# RoboRIOSPIBreakout.net
KiCad netlist of a schematic drawn in Altium Designer
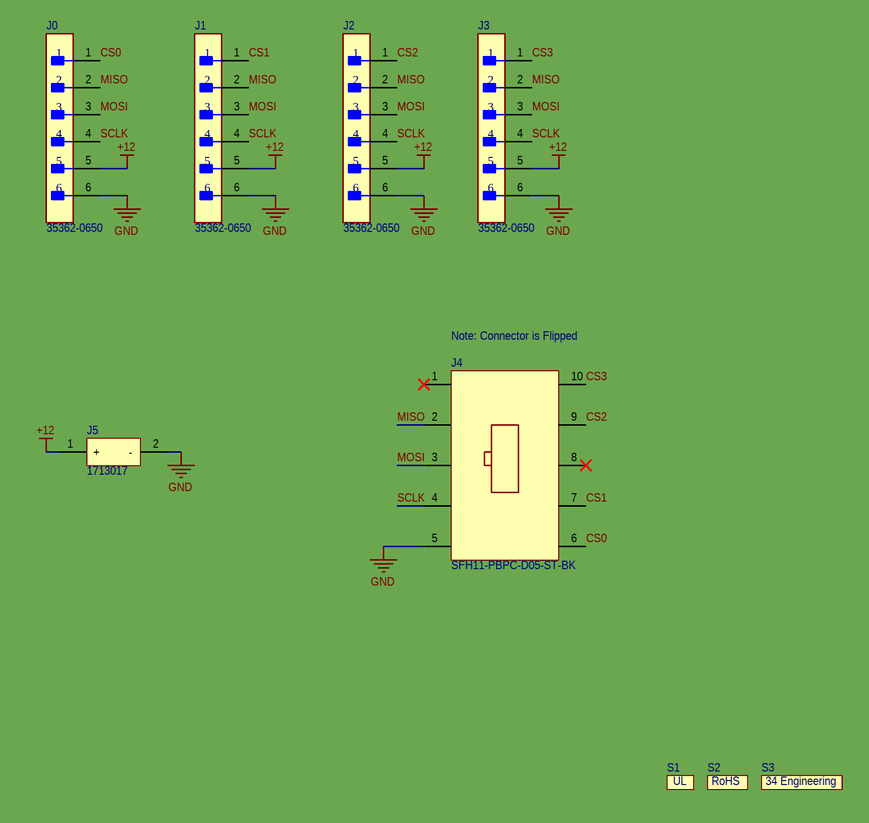
[diagram p0: RoboRIOSPIBreakout.SchDoc]

(export (version "E")
  (design (tool "Eeschema 10.0.6"))
  (components
    (comp (ref "J0")
      (value "35362-0650")
      (footprint "FP-35362-0650-MFG")
      (description "CONN HEADER VERT 6POS 2MM")
      (libsource (lib "Altium Content Vault") (part "f2cb566baf1c37ab5a3b8e90bbeafd6"))
    )
    (comp (ref "J1")
      (value "35362-0650")
      (footprint "FP-35362-0650-MFG")
      (description "CONN HEADER VERT 6POS 2MM")
      (libsource (lib "Altium Content Vault") (part "f2cb566baf1c37ab5a3b8e90bbeafd6"))
    )
    (comp (ref "J2")
      (value "35362-0650")
      (footprint "FP-35362-0650-MFG")
      (description "CONN HEADER VERT 6POS 2MM")
      (libsource (lib "Altium Content Vault") (part "f2cb566baf1c37ab5a3b8e90bbeafd6"))
    )
    (comp (ref "J3")
      (value "35362-0650")
      (footprint "FP-35362-0650-MFG")
      (description "CONN HEADER VERT 6POS 2MM")
      (libsource (lib "Altium Content Vault") (part "f2cb566baf1c37ab5a3b8e90bbeafd6"))
    )
    (comp (ref "J4")
      (value "SFH11-PBPC-D05-ST-BK")
      (footprint "SFH11-PBPC-D05-ST-BK")
      (description "Female, 10C, Straight .100\"CC; No Mt. w/Center Polarizing Key; PBT, Brass, Gold Flash, 105 C")
      (fields (field (name "MANUFACTURER") "Sullins"))
      (libsource (lib "Virtex") (part "SFH11-PBPC-D05-ST-BK"))
    )
    (comp (ref "J5")
      (value "1713017")
      (footprint "1713017")
      (description "PCB Terminal Push-In 3.5mm 16AWG 250V 8A 2 Position Combicon Compact Series")
      (fields (field (name "MANUFACTURER") "Phoenix Contact") (field (name "VOLTAGE") "300V"))
      (libsource (lib "Virtex") (part "1713017"))
    )
    (comp (ref "S1") (value "~") (footprint "UL") (libsource (lib "Virtex") (part "UL")))
    (comp (ref "S2") (value "~") (footprint "RoHS") (libsource (lib "Virtex") (part "RoHS")))
    (comp (ref "S3")
      (value "~")
      (footprint "34EngineeringLogo")
      (description "34 Engineering Silkscreen Logo")
      (libsource (lib "Virtex") (part "34EngineeringLogo"))
    )
  )
  (nets
    (net (code "1") (name "+12") (class "Default")
      (node (ref "J0") (pin "5") (pinfunction "5_5") (pintype "passive"))
      (node (ref "J1") (pin "5") (pinfunction "5_5") (pintype "passive"))
      (node (ref "J2") (pin "5") (pinfunction "5_5") (pintype "passive"))
      (node (ref "J3") (pin "5") (pinfunction "5_5") (pintype "passive"))
      (node (ref "J5") (pin "1") (pinfunction "+_1") (pintype "power_in"))
    )
    (net (code "2") (name "/CS0") (class "Default")
      (node (ref "J0") (pin "1") (pinfunction "1_1") (pintype "passive"))
      (node (ref "J4") (pin "6") (pintype "passive"))
    )
    (net (code "3") (name "/CS1") (class "Default")
      (node (ref "J1") (pin "1") (pinfunction "1_1") (pintype "passive"))
      (node (ref "J4") (pin "7") (pintype "passive"))
    )
    (net (code "4") (name "/CS2") (class "Default")
      (node (ref "J2") (pin "1") (pinfunction "1_1") (pintype "passive"))
      (node (ref "J4") (pin "9") (pintype "passive"))
    )
    (net (code "5") (name "/CS3") (class "Default")
      (node (ref "J3") (pin "1") (pinfunction "1_1") (pintype "passive"))
      (node (ref "J4") (pin "10") (pintype "passive"))
    )
    (net (code "6") (name "/MISO") (class "Default")
      (node (ref "J0") (pin "2") (pinfunction "2_2") (pintype "passive"))
      (node (ref "J1") (pin "2") (pinfunction "2_2") (pintype "passive"))
      (node (ref "J2") (pin "2") (pinfunction "2_2") (pintype "passive"))
      (node (ref "J3") (pin "2") (pinfunction "2_2") (pintype "passive"))
      (node (ref "J4") (pin "2") (pintype "passive"))
    )
    (net (code "7") (name "/MOSI") (class "Default")
      (node (ref "J0") (pin "3") (pinfunction "3_3") (pintype "passive"))
      (node (ref "J1") (pin "3") (pinfunction "3_3") (pintype "passive"))
      (node (ref "J2") (pin "3") (pinfunction "3_3") (pintype "passive"))
      (node (ref "J3") (pin "3") (pinfunction "3_3") (pintype "passive"))
      (node (ref "J4") (pin "3") (pintype "passive"))
    )
    (net (code "8") (name "/SCLK") (class "Default")
      (node (ref "J0") (pin "4") (pinfunction "4_4") (pintype "passive"))
      (node (ref "J1") (pin "4") (pinfunction "4_4") (pintype "passive"))
      (node (ref "J2") (pin "4") (pinfunction "4_4") (pintype "passive"))
      (node (ref "J3") (pin "4") (pinfunction "4_4") (pintype "passive"))
      (node (ref "J4") (pin "4") (pintype "passive"))
    )
    (net (code "9") (name "GND") (class "Default")
      (node (ref "J0") (pin "6") (pinfunction "6_6") (pintype "passive"))
      (node (ref "J1") (pin "6") (pinfunction "6_6") (pintype "passive"))
      (node (ref "J2") (pin "6") (pinfunction "6_6") (pintype "passive"))
      (node (ref "J3") (pin "6") (pinfunction "6_6") (pintype "passive"))
      (node (ref "J4") (pin "5") (pintype "passive"))
      (node (ref "J5") (pin "2") (pinfunction "-_2") (pintype "power_in"))
    )
    (net (code "10") (name "unconnected-(J4-Pad1)") (class "Default")
      (node (ref "J4") (pin "1") (pintype "passive+no_connect"))
    )
    (net (code "11") (name "unconnected-(J4-Pad8)") (class "Default")
      (node (ref "J4") (pin "8") (pintype "passive+no_connect"))
    )
  )
)
